# arduino_Uno_Rev3-02-TH.net
KiCad netlist of a schematic drawn in EAGLE
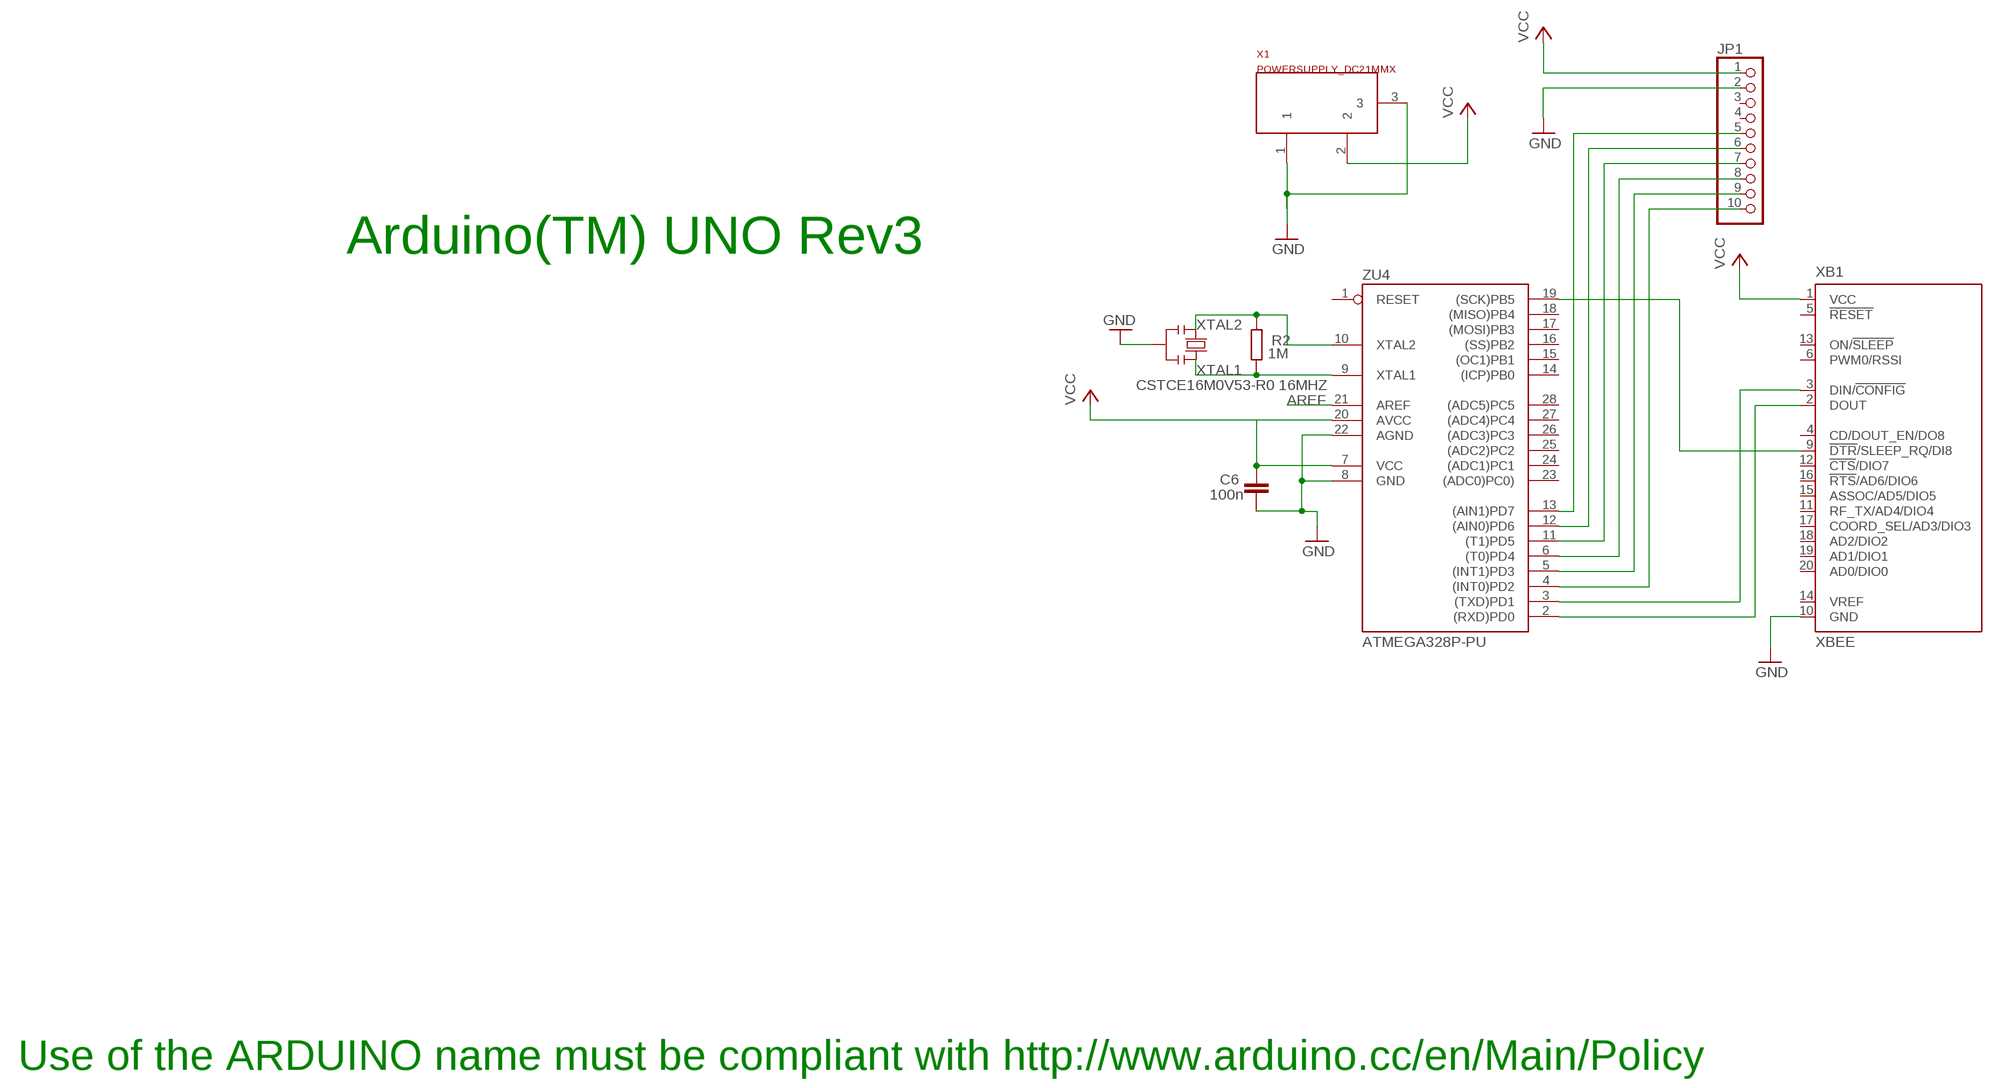
[diagram p0: schematic, sheet 1]

(export (version "E")
  (design (tool "Eeschema 10.0.6"))
  (components
    (comp (ref "C6")
      (value "100n")
      (footprint "eagle-import:C0603-ROUND")
      (libsource (lib "eagle-import") (part "C-EU0603-RND"))
    )
    (comp (ref "JP1")
      (value "PINHD-1X10")
      (footprint "eagle-import:1X10")
      (libsource (lib "eagle-import") (part "PINHD-1X10"))
    )
    (comp (ref "R2")
      (value "1M")
      (footprint "eagle-import:R0603-ROUND")
      (libsource (lib "eagle-import") (part "R-EU_R0603"))
    )
    (comp (ref "X1")
      (value "POWERSUPPLY_DC21MMX")
      (footprint "eagle-import:POWERSUPPLY_DC-21MM")
      (libsource (lib "eagle-import") (part "POWERSUPPLY_DC21MMX"))
    )
    (comp (ref "XB1")
      (value "XBEE")
      (footprint "eagle-import:XBEE")
      (fields (field (name "MPN") "XBP24-Z7UIT-004"))
      (libsource (lib "eagle-import") (part "XBEE"))
    )
    (comp (ref "Y2")
      (value "CSTCE16M0V53-R0 16MHZ")
      (footprint "eagle-import:RESONATOR")
      (libsource (lib "eagle-import") (part "RESONATORMU"))
    )
    (comp (ref "ZU4")
      (value "ATMEGA328P-PU")
      (footprint "eagle-import:DIL28-3")
      (libsource (lib "eagle-import") (part "ATMEGA328P-PU"))
    )
  )
  (nets
    (net (code "1") (name "/AREF") (class "Default")
      (node (ref "ZU4") (pin "21") (pinfunction "AREF_21") (pintype "passive"))
    )
    (net (code "2") (name "/XTAL1") (class "Default")
      (node (ref "R2") (pin "1") (pinfunction "1_1") (pintype "passive"))
      (node (ref "Y2") (pin "3") (pinfunction "3_3") (pintype "passive"))
      (node (ref "ZU4") (pin "9") (pinfunction "XTAL1_9") (pintype "bidirectional"))
    )
    (net (code "3") (name "/XTAL2") (class "Default")
      (node (ref "R2") (pin "2") (pinfunction "2_2") (pintype "passive"))
      (node (ref "Y2") (pin "1") (pinfunction "1_1") (pintype "passive"))
      (node (ref "ZU4") (pin "10") (pinfunction "XTAL2_10") (pintype "bidirectional"))
    )
    (net (code "4") (name "GND") (class "Default")
      (node (ref "C6") (pin "1") (pinfunction "1_1") (pintype "passive"))
      (node (ref "JP1") (pin "2") (pinfunction "2_2") (pintype "passive"))
      (node (ref "X1") (pin "1") (pinfunction "1_1") (pintype "power_in"))
      (node (ref "X1") (pin "3") (pinfunction "3_3") (pintype "power_in"))
      (node (ref "XB1") (pin "10") (pinfunction "GND_10") (pintype "power_in"))
      (node (ref "Y2") (pin "2") (pinfunction "2_2") (pintype "passive"))
      (node (ref "ZU4") (pin "22") (pinfunction "AGND_22") (pintype "power_in"))
      (node (ref "ZU4") (pin "8") (pinfunction "GND_8") (pintype "power_in"))
    )
    (net (code "5") (name "Net-(XB1-DIN{slash}~{CONFIG})") (class "Default")
      (node (ref "XB1") (pin "3") (pinfunction "DIN/~{CONFIG}_3") (pintype "input"))
      (node (ref "ZU4") (pin "3") (pinfunction "(TXD)PD1_3") (pintype "bidirectional"))
    )
    (net (code "6") (name "Net-(XB1-DOUT)") (class "Default")
      (node (ref "XB1") (pin "2") (pinfunction "DOUT_2") (pintype "output"))
      (node (ref "ZU4") (pin "2") (pinfunction "(RXD)PD0_2") (pintype "bidirectional"))
    )
    (net (code "7") (name "Net-(XB1-~{DTR}{slash}SLEEP_RQ{slash}DI8)") (class "Default")
      (node (ref "XB1") (pin "9") (pinfunction "~{DTR}/SLEEP_RQ/DI8_9") (pintype "bidirectional"))
      (node (ref "ZU4") (pin "19") (pinfunction "(SCK)PB5_19") (pintype "bidirectional"))
    )
    (net (code "8") (name "Net-(ZU4-(AIN0)PD6)") (class "Default")
      (node (ref "JP1") (pin "6") (pinfunction "6_6") (pintype "passive"))
      (node (ref "ZU4") (pin "12") (pinfunction "(AIN0)PD6_12") (pintype "bidirectional"))
    )
    (net (code "9") (name "Net-(ZU4-(AIN1)PD7)") (class "Default")
      (node (ref "JP1") (pin "5") (pinfunction "5_5") (pintype "passive"))
      (node (ref "ZU4") (pin "13") (pinfunction "(AIN1)PD7_13") (pintype "bidirectional"))
    )
    (net (code "10") (name "Net-(ZU4-(INT0)PD2)") (class "Default")
      (node (ref "JP1") (pin "10") (pinfunction "10_10") (pintype "passive"))
      (node (ref "ZU4") (pin "4") (pinfunction "(INT0)PD2_4") (pintype "bidirectional"))
    )
    (net (code "11") (name "Net-(ZU4-(INT1)PD3)") (class "Default")
      (node (ref "JP1") (pin "9") (pinfunction "9_9") (pintype "passive"))
      (node (ref "ZU4") (pin "5") (pinfunction "(INT1)PD3_5") (pintype "bidirectional"))
    )
    (net (code "12") (name "Net-(ZU4-(T0)PD4)") (class "Default")
      (node (ref "JP1") (pin "8") (pinfunction "8_8") (pintype "passive"))
      (node (ref "ZU4") (pin "6") (pinfunction "(T0)PD4_6") (pintype "bidirectional"))
    )
    (net (code "13") (name "Net-(ZU4-(T1)PD5)") (class "Default")
      (node (ref "JP1") (pin "7") (pinfunction "7_7") (pintype "passive"))
      (node (ref "ZU4") (pin "11") (pinfunction "(T1)PD5_11") (pintype "bidirectional"))
    )
    (net (code "14") (name "VCC") (class "Default")
      (node (ref "C6") (pin "2") (pinfunction "2_2") (pintype "passive"))
      (node (ref "JP1") (pin "1") (pinfunction "1_1") (pintype "passive"))
      (node (ref "X1") (pin "2") (pinfunction "2_2") (pintype "power_in"))
      (node (ref "XB1") (pin "1") (pinfunction "VCC_1") (pintype "power_in"))
      (node (ref "ZU4") (pin "20") (pinfunction "AVCC_20") (pintype "power_in"))
      (node (ref "ZU4") (pin "7") (pinfunction "VCC_7") (pintype "power_in"))
    )
    (net (code "15") (name "unconnected-(JP1-Pad3)") (class "Default")
      (node (ref "JP1") (pin "3") (pinfunction "3_3") (pintype "passive"))
    )
    (net (code "16") (name "unconnected-(JP1-Pad4)") (class "Default")
      (node (ref "JP1") (pin "4") (pinfunction "4_4") (pintype "passive"))
    )
    (net (code "17") (name "unconnected-(XB1-AD0{slash}DIO0-Pad20)") (class "Default")
      (node (ref "XB1") (pin "20") (pinfunction "AD0/DIO0_20") (pintype "bidirectional"))
    )
    (net (code "18") (name "unconnected-(XB1-AD1{slash}DIO1-Pad19)") (class "Default")
      (node (ref "XB1") (pin "19") (pinfunction "AD1/DIO1_19") (pintype "bidirectional"))
    )
    (net (code "19") (name "unconnected-(XB1-AD2{slash}DIO2-Pad18)") (class "Default")
      (node (ref "XB1") (pin "18") (pinfunction "AD2/DIO2_18") (pintype "bidirectional"))
    )
    (net (code "20") (name "unconnected-(XB1-ASSOC{slash}AD5{slash}DIO5-Pad15)") (class "Default")
      (node (ref "XB1") (pin "15") (pinfunction "ASSOC/AD5/DIO5_15") (pintype "bidirectional"))
    )
    (net (code "21") (name "unconnected-(XB1-CD{slash}DOUT_EN{slash}DO8-Pad4)") (class "Default")
      (node (ref "XB1") (pin "4") (pinfunction "CD/DOUT_EN/DO8_4") (pintype "output"))
    )
    (net (code "22") (name "unconnected-(XB1-COORD_SEL{slash}AD3{slash}DIO3-Pad17)") (class "Default")
      (node (ref "XB1") (pin "17") (pinfunction "COORD_SEL/AD3/DIO3_17") (pintype "bidirectional"))
    )
    (net (code "23") (name "unconnected-(XB1-ON{slash}~{SLEEP}-Pad13)") (class "Default")
      (node (ref "XB1") (pin "13") (pinfunction "ON/~{SLEEP}_13") (pintype "output"))
    )
    (net (code "24") (name "unconnected-(XB1-PWM0{slash}RSSI-Pad6)") (class "Default")
      (node (ref "XB1") (pin "6") (pinfunction "PWM0/RSSI_6") (pintype "output"))
    )
    (net (code "25") (name "unconnected-(XB1-RF_TX{slash}AD4{slash}DIO4-Pad11)") (class "Default")
      (node (ref "XB1") (pin "11") (pinfunction "RF_TX/AD4/DIO4_11") (pintype "bidirectional"))
    )
    (net (code "26") (name "unconnected-(XB1-VREF-Pad14)") (class "Default")
      (node (ref "XB1") (pin "14") (pinfunction "VREF_14") (pintype "input"))
    )
    (net (code "27") (name "unconnected-(XB1-~{CTS}{slash}DIO7-Pad12)") (class "Default")
      (node (ref "XB1") (pin "12") (pinfunction "~{CTS}/DIO7_12") (pintype "bidirectional"))
    )
    (net (code "28") (name "unconnected-(XB1-~{RESET}-Pad5)") (class "Default")
      (node (ref "XB1") (pin "5") (pinfunction "~{RESET}_5") (pintype "input"))
    )
    (net (code "29") (name "unconnected-(XB1-~{RTS}{slash}AD6{slash}DIO6-Pad16)") (class "Default")
      (node (ref "XB1") (pin "16") (pinfunction "~{RTS}/AD6/DIO6_16") (pintype "bidirectional"))
    )
    (net (code "30") (name "unconnected-(ZU4-(ADC0)PC0)-Pad23)") (class "Default")
      (node (ref "ZU4") (pin "23") (pinfunction "(ADC0)PC0)_23") (pintype "bidirectional"))
    )
    (net (code "31") (name "unconnected-(ZU4-(ADC1)PC1-Pad24)") (class "Default")
      (node (ref "ZU4") (pin "24") (pinfunction "(ADC1)PC1_24") (pintype "bidirectional"))
    )
    (net (code "32") (name "unconnected-(ZU4-(ADC2)PC2-Pad25)") (class "Default")
      (node (ref "ZU4") (pin "25") (pinfunction "(ADC2)PC2_25") (pintype "bidirectional"))
    )
    (net (code "33") (name "unconnected-(ZU4-(ADC3)PC3-Pad26)") (class "Default")
      (node (ref "ZU4") (pin "26") (pinfunction "(ADC3)PC3_26") (pintype "bidirectional"))
    )
    (net (code "34") (name "unconnected-(ZU4-(ADC4)PC4-Pad27)") (class "Default")
      (node (ref "ZU4") (pin "27") (pinfunction "(ADC4)PC4_27") (pintype "bidirectional"))
    )
    (net (code "35") (name "unconnected-(ZU4-(ADC5)PC5-Pad28)") (class "Default")
      (node (ref "ZU4") (pin "28") (pinfunction "(ADC5)PC5_28") (pintype "bidirectional"))
    )
    (net (code "36") (name "unconnected-(ZU4-(ICP)PB0-Pad14)") (class "Default")
      (node (ref "ZU4") (pin "14") (pinfunction "(ICP)PB0_14") (pintype "bidirectional"))
    )
    (net (code "37") (name "unconnected-(ZU4-(MISO)PB4-Pad18)") (class "Default")
      (node (ref "ZU4") (pin "18") (pinfunction "(MISO)PB4_18") (pintype "bidirectional"))
    )
    (net (code "38") (name "unconnected-(ZU4-(MOSI)PB3-Pad17)") (class "Default")
      (node (ref "ZU4") (pin "17") (pinfunction "(MOSI)PB3_17") (pintype "bidirectional"))
    )
    (net (code "39") (name "unconnected-(ZU4-(OC1)PB1-Pad15)") (class "Default")
      (node (ref "ZU4") (pin "15") (pinfunction "(OC1)PB1_15") (pintype "bidirectional"))
    )
    (net (code "40") (name "unconnected-(ZU4-(SS)PB2-Pad16)") (class "Default")
      (node (ref "ZU4") (pin "16") (pinfunction "(SS)PB2_16") (pintype "bidirectional"))
    )
    (net (code "41") (name "unconnected-(ZU4-RESET-Pad1)") (class "Default")
      (node (ref "ZU4") (pin "1") (pinfunction "RESET_1") (pintype "input"))
    )
  )
)
